# DIMNode062013.net
KiCad netlist of a schematic drawn in Altium Designer
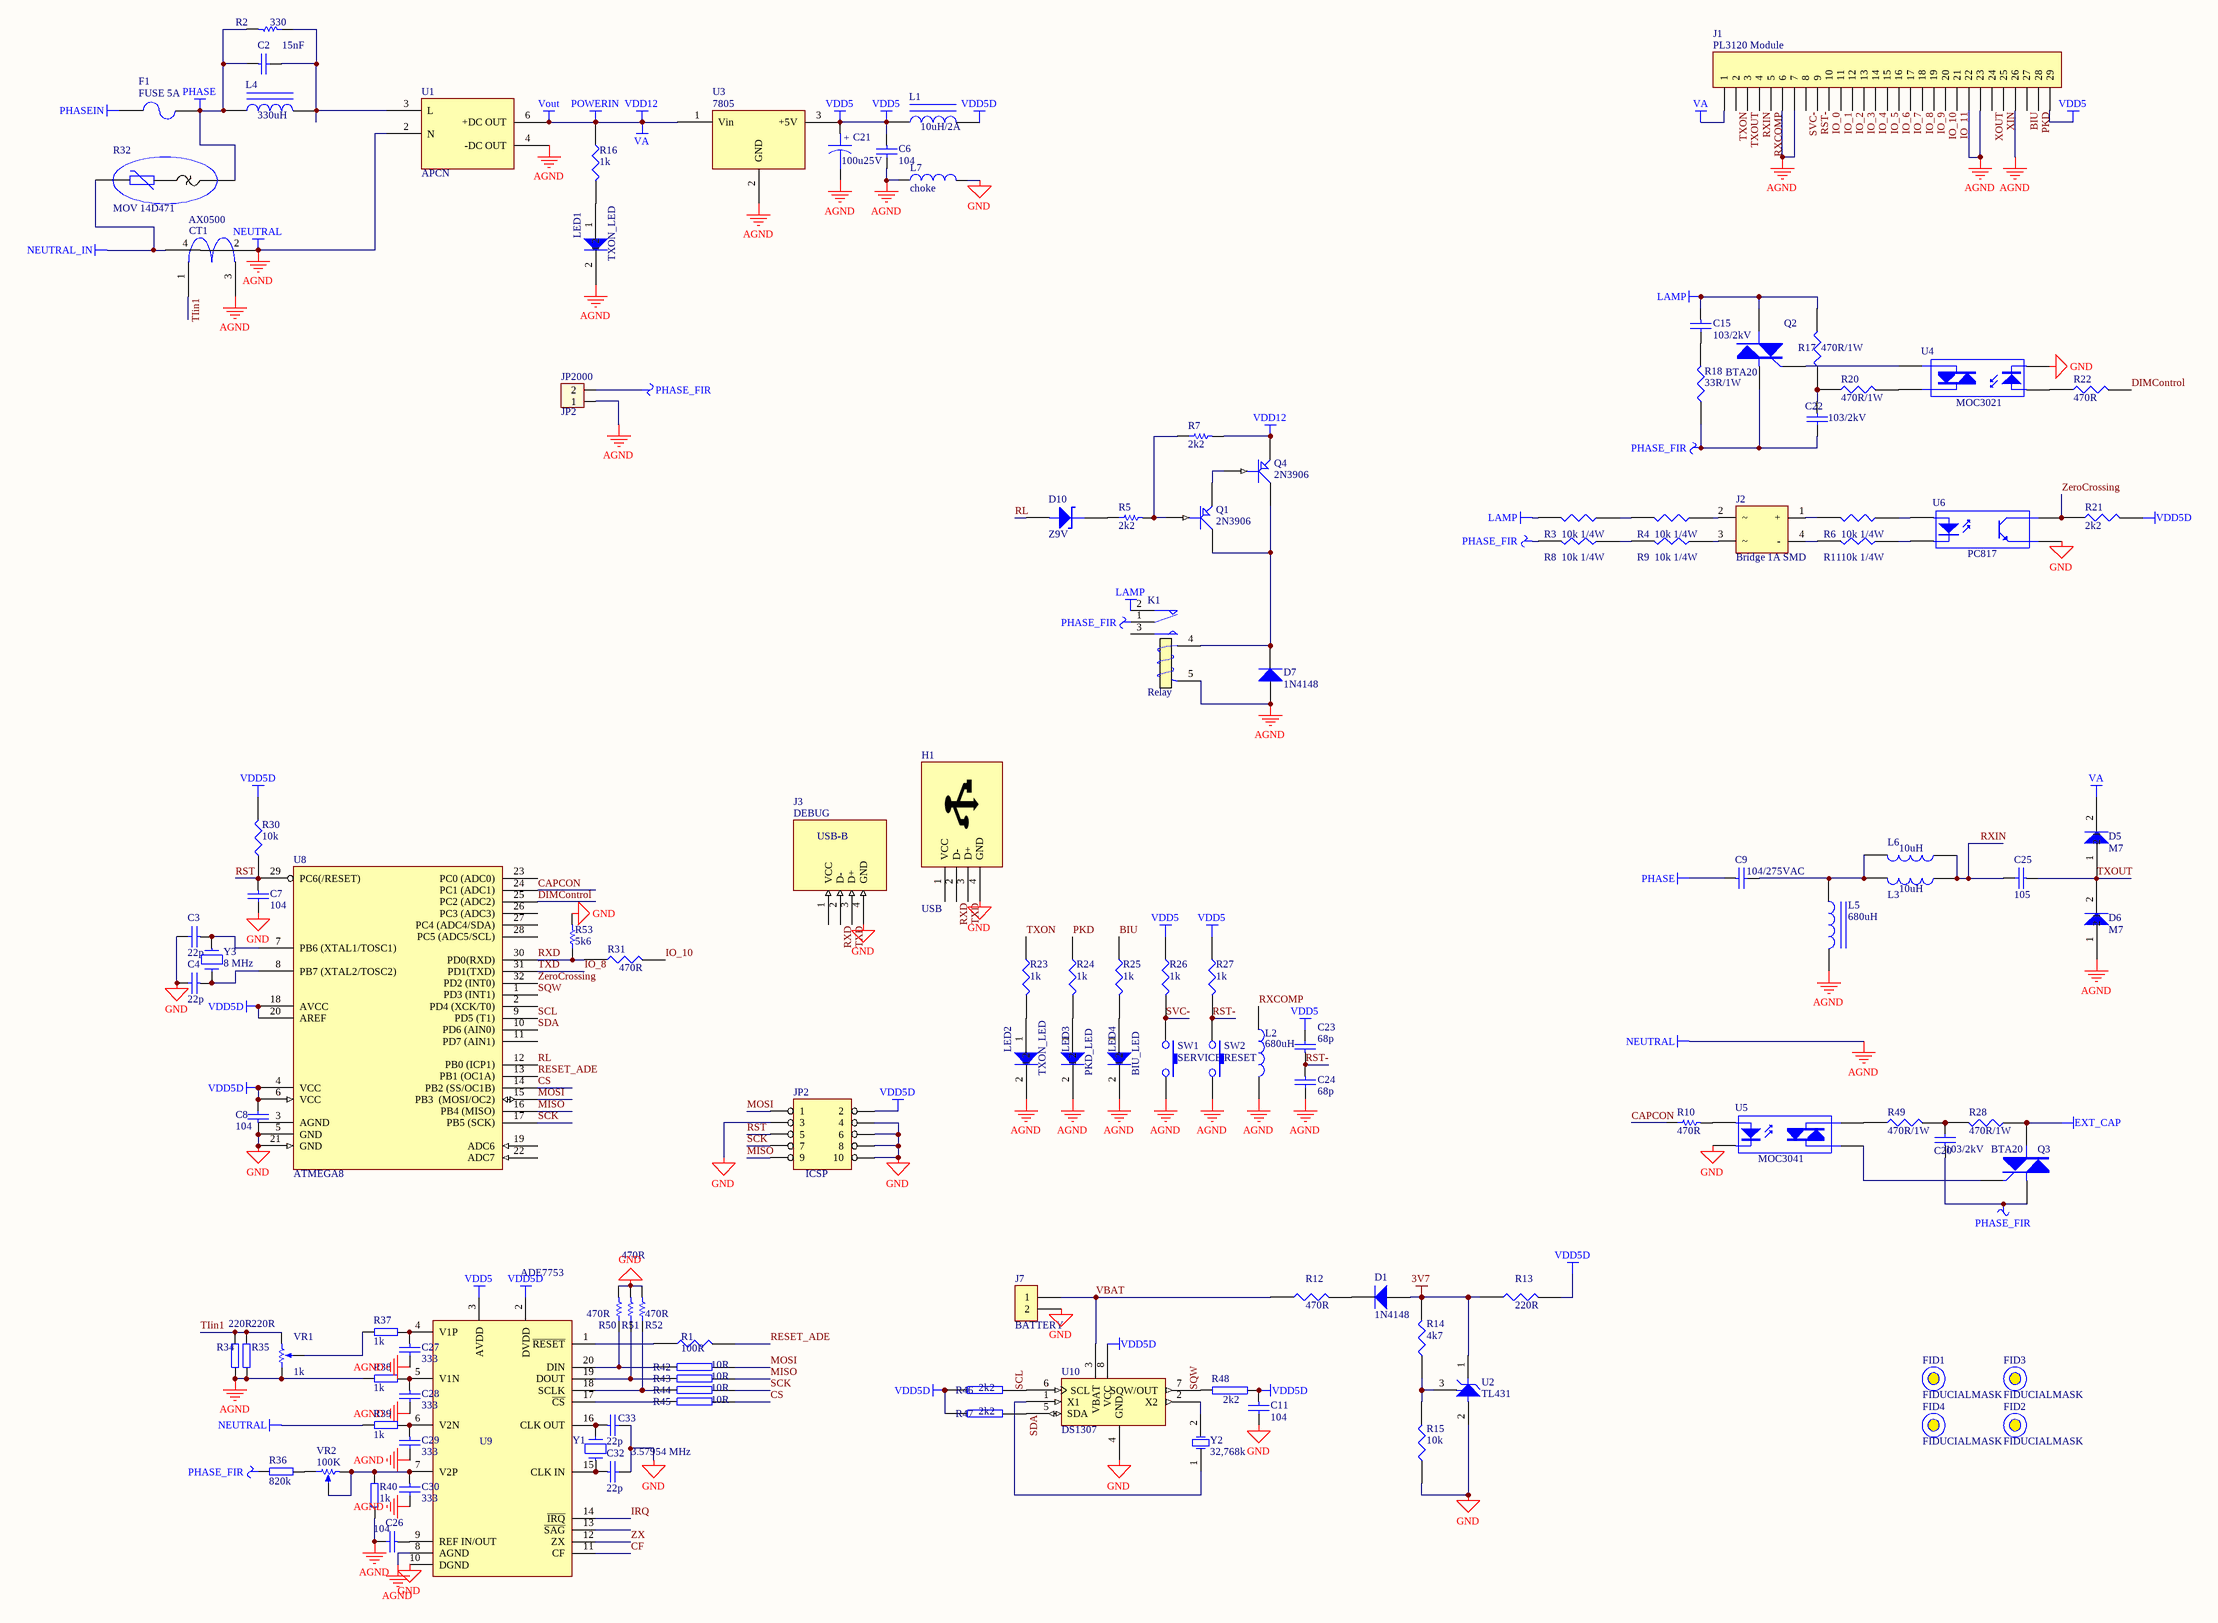
[diagram p0: DIMNode062013.SchDoc]

(export (version "E")
  (design (tool "Eeschema 10.0.6"))
  (components
    (comp (ref "C2")
      (value "15nF")
      (footprint "CAPNTO5.08-7.37x3.94")
      (description "Capacitor")
      (libsource (lib "*") (part "CAP"))
    )
    (comp (ref "C3") (value "22p") (footprint "2012[0805]") (libsource (lib "") (part "CAP_1")))
    (comp (ref "C4") (value "22p") (footprint "2012[0805]") (libsource (lib "") (part "CAP_1")))
    (comp (ref "C6")
      (value "104")
      (footprint "2012[0805]")
      (description "Capacitor")
      (libsource (lib "*") (part "CAP"))
    )
    (comp (ref "C7")
      (value "104")
      (footprint "2012[0805]")
      (description "Capacitor")
      (libsource (lib "*") (part "CAP"))
    )
    (comp (ref "C8")
      (value "104")
      (footprint "2012[0805]")
      (description "Capacitor")
      (libsource (lib "*") (part "CAP"))
    )
    (comp (ref "C9")
      (value "104/275VAC")
      (footprint "100n400v")
      (description "Capacitor")
      (libsource (lib "*") (part "CAP"))
    )
    (comp (ref "C11")
      (value "104")
      (footprint "2012[0805]")
      (description "Capacitor")
      (libsource (lib "*") (part "CAP"))
    )
    (comp (ref "C15")
      (value "103/2kV")
      (footprint "104TO")
      (description "Capacitor")
      (libsource (lib "*") (part "CAP"))
    )
    (comp (ref "C20")
      (value "103/2kV")
      (footprint "104TO")
      (description "Capacitor")
      (libsource (lib "*") (part "CAP"))
    )
    (comp (ref "C21")
      (value "100u25V")
      (footprint "TC7360-2924")
      (description "Capacitor")
      (libsource (lib "*") (part "CAPACITOR POL"))
    )
    (comp (ref "C22")
      (value "103/2kV")
      (footprint "104TO")
      (description "Capacitor")
      (libsource (lib "*") (part "CAP"))
    )
    (comp (ref "C23")
      (value "68p")
      (footprint "2012[0805]")
      (description "Capacitor")
      (libsource (lib "*") (part "CAP"))
    )
    (comp (ref "C24")
      (value "68p")
      (footprint "2012[0805]")
      (description "Capacitor")
      (libsource (lib "*") (part "CAP"))
    )
    (comp (ref "C25")
      (value "105")
      (footprint "CSIP3")
      (description "Capacitor")
      (libsource (lib "*") (part "CAP"))
    )
    (comp (ref "C26") (value "104") (footprint "2012[0805]") (libsource (lib "") (part "CAP_1")))
    (comp (ref "C27") (value "333") (footprint "2012[0805]") (libsource (lib "") (part "CAP_1")))
    (comp (ref "C28") (value "333") (footprint "2012[0805]") (libsource (lib "") (part "CAP_1")))
    (comp (ref "C29") (value "333") (footprint "2012[0805]") (libsource (lib "") (part "CAP_1")))
    (comp (ref "C30") (value "333") (footprint "2012[0805]") (libsource (lib "") (part "CAP_1")))
    (comp (ref "C32") (value "22p") (footprint "2012[0805]") (libsource (lib "") (part "CAP_1")))
    (comp (ref "C33") (value "22p") (footprint "2012[0805]") (libsource (lib "") (part "CAP_1")))
    (comp (ref "CT1") (value "AX0500") (footprint "CT-NHO") (libsource (lib "Schlib1") (part "AX-0500")))
    (comp (ref "D1")
      (value "1N4148")
      (footprint "SOD-80/MLL34")
      (description "1 Amp General Purpose Rectifier")
      (fields (field (name "PUBLISHER") "Altium Limited"))
      (libsource (lib "*") (part "Diode 1N4007"))
    )
    (comp (ref "D5") (value "M7") (footprint "MELF-D5022-2009") (libsource (lib "*") (part "DIODE")))
    (comp (ref "D6") (value "M7") (footprint "MELF-D5022-2009") (libsource (lib "*") (part "DIODE")))
    (comp (ref "D7")
      (value "1N4148")
      (footprint "SOD-80/MLL34")
      (description "1 Amp General Purpose Rectifier")
      (fields (field (name "PUBLISHER") "Altium Limited"))
      (libsource (lib "*") (part "Diode 1N4007"))
    )
    (comp (ref "D10")
      (value "Z9V")
      (footprint "SOD-80/MLL34")
      (description "Zener Diode")
      (libsource (lib "*") (part "ZENER2"))
    )
    (comp (ref "F1")
      (value "FUSE 5A")
      (footprint "FUSE2")
      (description "Fuse")
      (libsource (lib "*") (part "FUSE2"))
    )
    (comp (ref "FID1")
      (value "FIDUCIALMASK")
      (footprint "FIDUCIALMASK")
      (libsource (lib "*") (part "FIDUCIALMASK"))
    )
    (comp (ref "FID2")
      (value "FIDUCIALMASK")
      (footprint "FIDUCIALMASK")
      (libsource (lib "*") (part "FIDUCIALMASK"))
    )
    (comp (ref "FID3")
      (value "FIDUCIALMASK")
      (footprint "FIDUCIALMASK")
      (libsource (lib "*") (part "FIDUCIALMASK"))
    )
    (comp (ref "FID4")
      (value "FIDUCIALMASK")
      (footprint "FIDUCIALMASK")
      (libsource (lib "*") (part "FIDUCIALMASK"))
    )
    (comp (ref "H1") (value "USB") (footprint "USB-B-STRANGE") (libsource (lib "Schematic") (part "USB")))
    (comp (ref "J1")
      (value "PL3120 Module")
      (footprint "ECHELONMODULE")
      (description "Connector")
      (libsource (lib "*") (part "CON29"))
    )
    (comp (ref "J2")
      (value "Bridge 1A SMD")
      (footprint "CAUSMD")
      (description "Diode Bridge")
      (libsource (lib "Schematic") (part "Diode Bridge Flate"))
    )
    (comp (ref "J3") (value "DEBUG") (footprint "SJ-3515") (libsource (lib "*") (part "USB_B")))
    (comp (ref "J7")
      (value "BATTERY")
      (footprint "pincucao")
      (description "Connector")
      (libsource (lib "*") (part "CON2"))
    )
    (comp (ref "JP2") (value "ICSP") (footprint "IDC10") (libsource (lib "*") (part "HEADER 5X2")))
    (comp (ref "JP2000")
      (value "JP2")
      (footprint "HED2")
      (description "Connector 2")
      (libsource (lib "syhaunguyen") (part "Con2"))
    )
    (comp (ref "K1")
      (value "Relay")
      (footprint "Relayvuong")
      (description "SPDT Relay")
      (fields (field (name "PUBLISHER") "Altium Limited"))
      (libsource (lib "*") (part "Relay"))
    )
    (comp (ref "L1") (value "10uH/2A") (libsource (lib "*") (part "INDUCTOR IRON")))
    (comp (ref "L2") (value "680uH") (footprint "AXIAL0.4") (libsource (lib "*") (part "INDUCTOR")))
    (comp (ref "L3") (value "10uH") (footprint "AXIAL0.4") (libsource (lib "*") (part "INDUCTOR")))
    (comp (ref "L4") (value "330uH") (footprint "CAMTRONDUNG") (libsource (lib "*") (part "INDUCTOR IRON")))
    (comp (ref "L5") (value "680uH") (footprint "axial0.4") (libsource (lib "*") (part "INDUCTOR IRON")))
    (comp (ref "L6") (value "10uH") (footprint "AXIAL0.4") (libsource (lib "*") (part "INDUCTOR")))
    (comp (ref "L7")
      (value "choke")
      (footprint "axial0.3")
      (fields (field (name "PUBLISHER") "Altium Limited"))
      (libsource (lib "Miscellaneous Devices") (part "Inductor"))
    )
    (comp (ref "LED1") (value "TXON_LED") (footprint "LED0805") (libsource (lib "*") (part "DIODE")))
    (comp (ref "LED2") (value "TXON_LED") (footprint "LED0805") (libsource (lib "*") (part "DIODE")))
    (comp (ref "LED3") (value "PKD_LED") (footprint "LED0805") (libsource (lib "*") (part "DIODE")))
    (comp (ref "LED4") (value "BIU_LED") (footprint "LED0805") (libsource (lib "*") (part "DIODE")))
    (comp (ref "Q1")
      (value "2N3906")
      (footprint "SOT-23")
      (description "PNP Transistor")
      (libsource (lib "*") (part "PNP1"))
    )
    (comp (ref "Q2") (value "BTA20") (footprint "TO254") (libsource (lib "*") (part "TRIAC")))
    (comp (ref "Q3") (value "BTA20") (footprint "TO254") (libsource (lib "*") (part "TRIAC")))
    (comp (ref "Q4")
      (value "2N3906")
      (footprint "SOT-23")
      (description "PNP Transistor")
      (libsource (lib "*") (part "PNP1"))
    )
    (comp (ref "R1") (value "100R") (footprint "2012[0805]") (libsource (lib "*") (part "RES1")))
    (comp (ref "R2")
      (value "330")
      (footprint "3216[1206]")
      (description "Semiconductor Resistor")
      (fields (field (name "PUBLISHER") "Altium Limited"))
      (libsource (lib "*") (part "Res Semi"))
    )
    (comp (ref "R3") (value "10k 1/4W") (footprint "3216[1206]") (libsource (lib "*") (part "RES1")))
    (comp (ref "R4") (value "10k 1/4W") (footprint "3216[1206]") (libsource (lib "*") (part "RES1")))
    (comp (ref "R5")
      (value "2k2")
      (footprint "2012[0805]")
      (description "Semiconductor Resistor")
      (fields (field (name "PUBLISHER") "Altium Limited"))
      (libsource (lib "*") (part "Res Semi"))
    )
    (comp (ref "R6") (value "10k 1/4W") (footprint "3216[1206]") (libsource (lib "*") (part "RES1")))
    (comp (ref "R7")
      (value "2k2")
      (footprint "2012[0805]")
      (description "Semiconductor Resistor")
      (fields (field (name "PUBLISHER") "Altium Limited"))
      (libsource (lib "*") (part "Res Semi"))
    )
    (comp (ref "R8") (value "10k 1/4W") (footprint "3216[1206]") (libsource (lib "*") (part "RES1")))
    (comp (ref "R9") (value "10k 1/4W") (footprint "3216[1206]") (libsource (lib "*") (part "RES1")))
    (comp (ref "R10")
      (value "470R")
      (footprint "2012[0805]")
      (description "Semiconductor Resistor")
      (fields (field (name "PUBLISHER") "Altium Limited"))
      (libsource (lib "*") (part "Res Semi"))
    )
    (comp (ref "R11") (value "10k 1/4W") (footprint "3216[1206]") (libsource (lib "*") (part "RES1")))
    (comp (ref "R12") (value "470R") (footprint "2012[0805]") (libsource (lib "*") (part "RES1")))
    (comp (ref "R13") (value "220R") (footprint "2012[0805]") (libsource (lib "*") (part "RES1")))
    (comp (ref "R14") (value "4k7") (footprint "2012[0805]") (libsource (lib "*") (part "RES1")))
    (comp (ref "R15") (value "10k") (footprint "2012[0805]") (libsource (lib "*") (part "RES1")))
    (comp (ref "R16") (value "1k") (footprint "2012[0805]") (libsource (lib "*") (part "RES1")))
    (comp (ref "R17") (value "470R/1W") (footprint "AXIAL0.5") (libsource (lib "*") (part "RES1")))
    (comp (ref "R18") (value "33R/1W") (footprint "R1W_dung") (libsource (lib "*") (part "RES1")))
    (comp (ref "R20") (value "470R/1W") (footprint "R1W_DUNG") (libsource (lib "*") (part "RES1")))
    (comp (ref "R21") (value "2k2") (footprint "2012[0805]") (libsource (lib "*") (part "RES1")))
    (comp (ref "R22") (value "470R") (footprint "2012[0805]") (libsource (lib "*") (part "RES1")))
    (comp (ref "R23") (value "1k") (footprint "2012[0805]") (libsource (lib "*") (part "RES1")))
    (comp (ref "R24") (value "1k") (footprint "2012[0805]") (libsource (lib "*") (part "RES1")))
    (comp (ref "R25") (value "1k") (footprint "2012[0805]") (libsource (lib "*") (part "RES1")))
    (comp (ref "R26") (value "1k") (footprint "2012[0805]") (libsource (lib "*") (part "RES1")))
    (comp (ref "R27") (value "1k") (footprint "2012[0805]") (libsource (lib "*") (part "RES1")))
    (comp (ref "R28") (value "470R/1W") (footprint "R1W_dung") (libsource (lib "*") (part "RES1")))
    (comp (ref "R30") (value "10k") (footprint "2012[0805]") (libsource (lib "*") (part "RES1")))
    (comp (ref "R31") (value "470R") (footprint "2012[0805]") (libsource (lib "*") (part "RES1")))
    (comp (ref "R32") (value "MOV 14D471") (footprint "MOV471") (libsource (lib "*") (part "MOV")))
    (comp (ref "R34") (value "220R") (footprint "2012[0805]") (libsource (lib "*") (part "RES2")))
    (comp (ref "R35") (value "220R") (footprint "2012[0805]") (libsource (lib "*") (part "RES2")))
    (comp (ref "R36") (value "820k") (footprint "1206") (libsource (lib "*") (part "RES2")))
    (comp (ref "R37") (value "1k") (footprint "2012[0805]") (libsource (lib "*") (part "RES2")))
    (comp (ref "R38") (value "1k") (footprint "2012[0805]") (libsource (lib "*") (part "RES2")))
    (comp (ref "R39") (value "1k") (footprint "2012[0805]") (libsource (lib "*") (part "RES2")))
    (comp (ref "R40") (value "1k") (footprint "2012[0805]") (libsource (lib "*") (part "RES2")))
    (comp (ref "R42") (value "10R") (footprint "2012[0805]") (libsource (lib "") (part "RES2_1")))
    (comp (ref "R43") (value "10R") (footprint "2012[0805]") (libsource (lib "") (part "RES2_1")))
    (comp (ref "R44") (value "10R") (footprint "2012[0805]") (libsource (lib "") (part "RES2_1")))
    (comp (ref "R45") (value "10R") (footprint "2012[0805]") (libsource (lib "") (part "RES2_1")))
    (comp (ref "R46") (value "2k2") (footprint "2012[0805]") (libsource (lib "") (part "RES2_1")))
    (comp (ref "R47") (value "2k2") (footprint "2012[0805]") (libsource (lib "") (part "RES2_1")))
    (comp (ref "R48") (value "2k2") (footprint "2012[0805]") (libsource (lib "") (part "RES2_2")))
    (comp (ref "R49") (value "470R/1W") (footprint "R1W_DUNG") (libsource (lib "*") (part "RES1")))
    (comp (ref "R50")
      (value "470R")
      (footprint "2012[0805]")
      (description "Semiconductor Resistor")
      (fields (field (name "PUBLISHER") "*"))
      (libsource (lib "*") (part "Res Semi"))
    )
    (comp (ref "R51")
      (value "470R")
      (footprint "2012[0805]")
      (description "Semiconductor Resistor")
      (fields (field (name "PUBLISHER") "*"))
      (libsource (lib "*") (part "Res Semi"))
    )
    (comp (ref "R52")
      (value "470R")
      (footprint "2012[0805]")
      (description "Semiconductor Resistor")
      (fields (field (name "PUBLISHER") "*"))
      (libsource (lib "*") (part "Res Semi"))
    )
    (comp (ref "R53")
      (value "5k6")
      (footprint "2012[0805]")
      (description "Semiconductor Resistor")
      (fields (field (name "PUBLISHER") "*"))
      (libsource (lib "*") (part "Res Semi"))
    )
    (comp (ref "SW1") (value "SERVICE") (footprint "CTCHIPNGANG") (libsource (lib "*") (part "SW-PB")))
    (comp (ref "SW2") (value "RESET") (footprint "CTCHIPNGANG") (libsource (lib "*") (part "SW-PB")))
    (comp (ref "U1") (value "APCN") (footprint "APCN") (libsource (lib "Node v2013") (part "Component_1")))
    (comp (ref "U2")
      (value "TL431")
      (footprint "TL431")
      (description "Adjustable Precision Shunt Regulator")
      (libsource (lib "*") (part "TL431"))
    )
    (comp (ref "U3") (value "7805") (footprint "J7805") (libsource (lib "*") (part "MC7805T")))
    (comp (ref "U4") (value "MOC3021") (footprint "DIP6") (libsource (lib "*") (part "OPTOTRIAC")))
    (comp (ref "U5") (value "MOC3041") (footprint "DIP6") (libsource (lib "*") (part "OPTOTRIAC")))
    (comp (ref "U6")
      (value "PC817")
      (footprint "TLP521")
      (description "Optoisolator")
      (libsource (lib "*") (part "OPTOISO1"))
    )
    (comp (ref "U8")
      (value "ATMEGA8")
      (footprint "ATMEGA8")
      (description "TQFP package")
      (libsource (lib "*") (part "ATMEGA8-A"))
    )
    (comp (ref "U9") (value "ADE7753") (footprint "ADE775X") (libsource (lib "*") (part "ADE775X")))
    (comp (ref "U10")
      (value "DS1307")
      (footprint "SO-8")
      (description "64x8 SERIAL REAL TIME CLOCK")
      (libsource (lib "*") (part "DS1307(8)"))
    )
    (comp (ref "VR1")
      (value "1k")
      (footprint "BTXANH")
      (description "Potentiometer")
      (fields (field (name "PUBLISHER") "*"))
      (libsource (lib "*") (part "RPot"))
    )
    (comp (ref "VR2")
      (value "100K")
      (footprint "BTXANH")
      (description "Potentiometer")
      (fields (field (name "PUBLISHER") "*"))
      (libsource (lib "*") (part "RPot"))
    )
    (comp (ref "Y1")
      (value "3.57954 MHz")
      (footprint "XTAL")
      (description "Crystal")
      (libsource (lib "*") (part "CRYSTAL"))
    )
    (comp (ref "Y2")
      (value "32,768k")
      (footprint "R38")
      (description "Crystal Oscillator")
      (fields (field (name "PUBLISHER") "Altium Limited"))
      (libsource (lib "Miscellaneous Devices") (part "XTAL"))
    )
    (comp (ref "Y3")
      (value "8 MHz")
      (footprint "XTAL")
      (description "Crystal")
      (libsource (lib "*") (part "CRYSTAL"))
    )
  )
  (nets
    (net (code "1") (name "/BIU") (class "Default")
      (node (ref "J1") (pin "27") (pinfunction "27_27") (pintype "passive"))
      (node (ref "R25") (pin "1") (pinfunction "1_1") (pintype "passive"))
    )
    (net (code "2") (name "/CAPCON") (class "Default")
      (node (ref "R10") (pin "1") (pinfunction "1_1") (pintype "passive"))
      (node (ref "U8") (pin "24") (pinfunction "PC1_(ADC1)_24") (pintype "passive"))
    )
    (net (code "3") (name "/CF") (class "Default")
      (node (ref "U9") (pin "11") (pinfunction "CF_11") (pintype "passive"))
    )
    (net (code "4") (name "/CS") (class "Default")
      (node (ref "R45") (pin "1") (pinfunction "1_1") (pintype "passive"))
      (node (ref "U8") (pin "14") (pinfunction "PB2_(SS/OC1B)_14") (pintype "passive"))
    )
    (net (code "5") (name "/DIMControl") (class "Default")
      (node (ref "R22") (pin "2") (pinfunction "2_2") (pintype "passive"))
      (node (ref "U8") (pin "25") (pinfunction "PC2_(ADC2)_25") (pintype "passive"))
    )
    (net (code "6") (name "/IO_0") (class "Default")
      (node (ref "J1") (pin "10") (pinfunction "10_10") (pintype "passive"))
    )
    (net (code "7") (name "/IO_1") (class "Default")
      (node (ref "J1") (pin "11") (pinfunction "11_11") (pintype "passive"))
    )
    (net (code "8") (name "/IO_2") (class "Default")
      (node (ref "J1") (pin "12") (pinfunction "12_12") (pintype "passive"))
    )
    (net (code "9") (name "/IO_3") (class "Default")
      (node (ref "J1") (pin "13") (pinfunction "13_13") (pintype "passive"))
    )
    (net (code "10") (name "/IO_4") (class "Default")
      (node (ref "J1") (pin "14") (pinfunction "14_14") (pintype "passive"))
    )
    (net (code "11") (name "/IO_5") (class "Default")
      (node (ref "J1") (pin "15") (pinfunction "15_15") (pintype "passive"))
    )
    (net (code "12") (name "/IO_6") (class "Default")
      (node (ref "J1") (pin "16") (pinfunction "16_16") (pintype "passive"))
    )
    (net (code "13") (name "/IO_7") (class "Default")
      (node (ref "J1") (pin "17") (pinfunction "17_17") (pintype "passive"))
    )
    (net (code "14") (name "/IO_8") (class "Default")
      (node (ref "H1") (pin "3") (pinfunction "D+_3") (pintype "passive"))
      (node (ref "J1") (pin "18") (pinfunction "18_18") (pintype "passive"))
      (node (ref "J3") (pin "3") (pinfunction "D+_3") (pintype "input"))
      (node (ref "U8") (pin "31") (pinfunction "PD1(TXD)_31") (pintype "passive"))
    )
    (net (code "15") (name "/IO_9") (class "Default")
      (node (ref "J1") (pin "19") (pinfunction "19_19") (pintype "passive"))
    )
    (net (code "16") (name "/IO_10") (class "Default")
      (node (ref "J1") (pin "20") (pinfunction "20_20") (pintype "passive"))
      (node (ref "R31") (pin "2") (pinfunction "2_2") (pintype "passive"))
    )
    (net (code "17") (name "/IO_11") (class "Default")
      (node (ref "J1") (pin "21") (pinfunction "21_21") (pintype "passive"))
    )
    (net (code "18") (name "/IRQ") (class "Default")
      (node (ref "U9") (pin "14") (pinfunction "~{IRQ}_14") (pintype "passive"))
    )
    (net (code "19") (name "/MISO") (class "Default")
      (node (ref "JP2") (pin "9") (pinfunction "9_9") (pintype "passive"))
      (node (ref "R43") (pin "1") (pinfunction "1_1") (pintype "passive"))
      (node (ref "U8") (pin "16") (pinfunction "PB4_(MISO)_16") (pintype "passive"))
    )
    (net (code "20") (name "/MOSI") (class "Default")
      (node (ref "JP2") (pin "1") (pinfunction "1_1") (pintype "passive"))
      (node (ref "R42") (pin "1") (pinfunction "1_1") (pintype "passive"))
      (node (ref "U8") (pin "15") (pinfunction "PB3__(MOSI/OC2)_15") (pintype "bidirectional"))
    )
    (net (code "21") (name "/PKD") (class "Default")
      (node (ref "J1") (pin "28") (pinfunction "28_28") (pintype "passive"))
      (node (ref "R24") (pin "1") (pinfunction "1_1") (pintype "passive"))
    )
    (net (code "22") (name "/RESET_ADE") (class "Default")
      (node (ref "R1") (pin "2") (pinfunction "2_2") (pintype "passive"))
      (node (ref "U8") (pin "13") (pinfunction "PB1_(OC1A)_13") (pintype "passive"))
    )
    (net (code "23") (name "/RL") (class "Default")
      (node (ref "D10") (pin "1") (pinfunction "A_1") (pintype "passive"))
      (node (ref "U8") (pin "12") (pinfunction "PB0_(ICP1)_12") (pintype "passive"))
    )
    (net (code "24") (name "/RST") (class "Default")
      (node (ref "C7") (pin "1") (pinfunction "1_1") (pintype "passive"))
      (node (ref "JP2") (pin "5") (pinfunction "5_5") (pintype "passive"))
      (node (ref "R30") (pin "1") (pinfunction "1_1") (pintype "passive"))
      (node (ref "U8") (pin "29") (pinfunction "PC6(/RESET)_29") (pintype "passive"))
    )
    (net (code "25") (name "/RST-") (class "Default")
      (node (ref "C23") (pin "1") (pinfunction "1_1") (pintype "passive"))
      (node (ref "C24") (pin "1") (pinfunction "1_1") (pintype "passive"))
      (node (ref "J1") (pin "9") (pinfunction "9_9") (pintype "passive"))
      (node (ref "R27") (pin "2") (pinfunction "2_2") (pintype "passive"))
      (node (ref "SW2") (pin "1") (pinfunction "1_1") (pintype "passive"))
    )
    (net (code "26") (name "/RXCOMP") (class "Default")
      (node (ref "J1") (pin "5") (pinfunction "5_5") (pintype "passive"))
      (node (ref "L2") (pin "1") (pinfunction "1_1") (pintype "passive"))
    )
    (net (code "27") (name "/RXD") (class "Default")
      (node (ref "H1") (pin "2") (pinfunction "D-_2") (pintype "passive"))
      (node (ref "J3") (pin "2") (pinfunction "D-_2") (pintype "input"))
      (node (ref "R31") (pin "1") (pinfunction "1_1") (pintype "passive"))
      (node (ref "R53") (pin "1") (pinfunction "1_1") (pintype "passive"))
      (node (ref "U8") (pin "30") (pinfunction "PD0(RXD)_30") (pintype "passive"))
    )
    (net (code "28") (name "/RXIN") (class "Default")
      (node (ref "C25") (pin "2") (pinfunction "2_2") (pintype "passive"))
      (node (ref "J1") (pin "4") (pinfunction "4_4") (pintype "passive"))
      (node (ref "L3") (pin "1") (pinfunction "1_1") (pintype "passive"))
      (node (ref "L6") (pin "1") (pinfunction "1_1") (pintype "passive"))
    )
    (net (code "29") (name "/SCK") (class "Default")
      (node (ref "JP2") (pin "7") (pinfunction "7_7") (pintype "passive"))
      (node (ref "R44") (pin "1") (pinfunction "1_1") (pintype "passive"))
      (node (ref "U8") (pin "17") (pinfunction "PB5_(SCK)_17") (pintype "passive"))
    )
    (net (code "30") (name "/SCL") (class "Default")
      (node (ref "R46") (pin "1") (pinfunction "1_1") (pintype "passive"))
      (node (ref "U10") (pin "6") (pinfunction "SCL_6") (pintype "input"))
      (node (ref "U8") (pin "9") (pinfunction "PD5_(T1)_9") (pintype "passive"))
    )
    (net (code "31") (name "/SDA") (class "Default")
      (node (ref "R47") (pin "1") (pinfunction "1_1") (pintype "passive"))
      (node (ref "U10") (pin "5") (pinfunction "SDA_5") (pintype "bidirectional"))
      (node (ref "U8") (pin "10") (pinfunction "PD6_(AIN0)_10") (pintype "passive"))
    )
    (net (code "32") (name "/SQW") (class "Default")
      (node (ref "R48") (pin "1") (pinfunction "1_1") (pintype "passive"))
      (node (ref "U10") (pin "7") (pinfunction "SQW/OUT_7") (pintype "output"))
      (node (ref "U8") (pin "1") (pinfunction "PD3_(INT1)_1") (pintype "passive"))
    )
    (net (code "33") (name "/SVC-") (class "Default")
      (node (ref "J1") (pin "8") (pinfunction "8_8") (pintype "passive"))
      (node (ref "R26") (pin "2") (pinfunction "2_2") (pintype "passive"))
      (node (ref "SW1") (pin "1") (pinfunction "1_1") (pintype "passive"))
    )
    (net (code "34") (name "/TIin1") (class "Default")
      (node (ref "CT1") (pin "1") (pinfunction "OUT1_1") (pintype "passive"))
      (node (ref "R34") (pin "2") (pinfunction "2_2") (pintype "passive"))
      (node (ref "R35") (pin "2") (pinfunction "2_2") (pintype "passive"))
      (node (ref "VR1") (pin "3") (pinfunction "BOT_3") (pintype "passive"))
    )
    (net (code "35") (name "/TXON") (class "Default")
      (node (ref "J1") (pin "2") (pinfunction "2_2") (pintype "passive"))
      (node (ref "R23") (pin "1") (pinfunction "1_1") (pintype "passive"))
    )
    (net (code "36") (name "/TXOUT") (class "Default")
      (node (ref "C25") (pin "1") (pinfunction "1_1") (pintype "passive"))
      (node (ref "D5") (pin "1") (pinfunction "1_1") (pintype "passive"))
      (node (ref "D6") (pin "2") (pinfunction "2_2") (pintype "passive"))
      (node (ref "J1") (pin "3") (pinfunction "3_3") (pintype "passive"))
    )
    (net (code "37") (name "/VBAT") (class "Default")
      (node (ref "J7") (pin "1") (pinfunction "1_1") (pintype "passive"))
      (node (ref "R12") (pin "1") (pinfunction "1_1") (pintype "passive"))
      (node (ref "U10") (pin "3") (pinfunction "VBAT_3") (pintype "power_in"))
    )
    (net (code "38") (name "/XIN") (class "Default")
      (node (ref "J1") (pin "25") (pinfunction "25_25") (pintype "passive"))
    )
    (net (code "39") (name "/XOUT") (class "Default")
      (node (ref "J1") (pin "24") (pinfunction "24_24") (pintype "passive"))
    )
    (net (code "40") (name "/ZX") (class "Default")
      (node (ref "U9") (pin "12") (pinfunction "ZX_12") (pintype "passive"))
    )
    (net (code "41") (name "/ZeroCrossing") (class "Default")
      (node (ref "R21") (pin "1") (pinfunction "1_1") (pintype "passive"))
      (node (ref "U6") (pin "3") (pinfunction "C_3") (pintype "passive"))
      (node (ref "U8") (pin "32") (pinfunction "PD2_(INT0)_32") (pintype "passive"))
    )
    (net (code "42") (name "3V7") (class "Default")
      (node (ref "D1") (pin "1") (pinfunction "A_1") (pintype "passive"))
      (node (ref "R13") (pin "1") (pinfunction "1_1") (pintype "passive"))
      (node (ref "R14") (pin "2") (pinfunction "2_2") (pintype "passive"))
      (node (ref "U2") (pin "1") (pinfunction "K_1") (pintype "passive"))
    )
    (net (code "43") (name "AGND") (class "Default")
      (node (ref "C21") (pin "2") (pinfunction "2_2") (pintype "passive"))
      (node (ref "C24") (pin "2") (pinfunction "2_2") (pintype "passive"))
      (node (ref "C26") (pin "2") (pinfunction "2_2") (pintype "passive"))
      (node (ref "C27") (pin "2") (pinfunction "2_2") (pintype "passive"))
      (node (ref "C28") (pin "2") (pinfunction "2_2") (pintype "passive"))
      (node (ref "C29") (pin "2") (pinfunction "2_2") (pintype "passive"))
      (node (ref "C30") (pin "2") (pinfunction "2_2") (pintype "passive"))
      (node (ref "C6") (pin "2") (pinfunction "2_2") (pintype "passive"))
      (node (ref "CT1") (pin "2") (pinfunction "ACin_2") (pintype "passive"))
      (node (ref "CT1") (pin "3") (pinfunction "OUT2_3") (pintype "passive"))
      (node (ref "D6") (pin "1") (pinfunction "1_1") (pintype "passive"))
      (node (ref "D7") (pin "1") (pinfunction "A_1") (pintype "passive"))
      (node (ref "J1") (pin "22") (pinfunction "22_22") (pintype "passive"))
      (node (ref "J1") (pin "23") (pinfunction "23_23") (pintype "passive"))
      (node (ref "J1") (pin "26") (pinfunction "26_26") (pintype "passive"))
      (node (ref "J1") (pin "6") (pinfunction "6_6") (pintype "passive"))
      (node (ref "J1") (pin "7") (pinfunction "7_7") (pintype "passive"))
      (node (ref "JP2000") (pin "1") (pinfunction "1_1") (pintype "passive"))
      (node (ref "K1") (pin "5") (pinfunction "T2_5") (pintype "passive"))
      (node (ref "L2") (pin "2") (pinfunction "2_2") (pintype "passive"))
      (node (ref "L5") (pin "2") (pinfunction "2_2") (pintype "passive"))
      (node (ref "L7") (pin "1") (pinfunction "1_1") (pintype "passive"))
      (node (ref "LED1") (pin "2") (pinfunction "2_2") (pintype "passive"))
      (node (ref "LED2") (pin "2") (pinfunction "2_2") (pintype "passive"))
      (node (ref "LED3") (pin "2") (pinfunction "2_2") (pintype "passive"))
      (node (ref "LED4") (pin "2") (pinfunction "2_2") (pintype "passive"))
      (node (ref "R34") (pin "1") (pinfunction "1_1") (pintype "passive"))
      (node (ref "R35") (pin "1") (pinfunction "1_1") (pintype "passive"))
      (node (ref "R38") (pin "2") (pinfunction "2_2") (pintype "passive"))
      (node (ref "R39") (pin "2") (pinfunction "2_2") (pintype "passive"))
      (node (ref "R40") (pin "1") (pinfunction "1_1") (pintype "passive"))
      (node (ref "SW1") (pin "2") (pinfunction "2_2") (pintype "passive"))
      (node (ref "SW2") (pin "2") (pinfunction "2_2") (pintype "passive"))
      (node (ref "U1") (pin "2") (pinfunction "N_2") (pintype "passive"))
      (node (ref "U1") (pin "4") (pinfunction "-DC_OUT_4") (pintype "passive"))
      (node (ref "U3") (pin "2") (pinfunction "GND_2") (pintype "passive"))
      (node (ref "U9") (pin "8") (pinfunction "AGND_8") (pintype "passive"))
      (node (ref "VR1") (pin "1") (pinfunction "TOP_1") (pintype "passive"))
    )
    (net (code "44") (name "EXT_CAP") (class "Default")
      (node (ref "Q3") (pin "2") (pinfunction "T_2") (pintype "passive"))
      (node (ref "R28") (pin "1") (pinfunction "1_1") (pintype "passive"))
    )
    (net (code "45") (name "GND") (class "Default")
      (node (ref "C11") (pin "2") (pinfunction "2_2") (pintype "passive"))
      (node (ref "C3") (pin "2") (pinfunction "2_2") (pintype "passive"))
      (node (ref "C32") (pin "2") (pinfunction "2_2") (pintype "passive"))
      (node (ref "C33") (pin "2") (pinfunction "2_2") (pintype "passive"))
      (node (ref "C4") (pin "2") (pinfunction "2_2") (pintype "passive"))
      (node (ref "C7") (pin "2") (pinfunction "2_2") (pintype "passive"))
      (node (ref "C8") (pin "1") (pinfunction "1_1") (pintype "passive"))
      (node (ref "H1") (pin "4") (pinfunction "GND_4") (pintype "passive"))
      (node (ref "J3") (pin "4") (pinfunction "GND_4") (pintype "input"))
      (node (ref "J7") (pin "2") (pinfunction "2_2") (pintype "passive"))
      (node (ref "JP2") (pin "10") (pinfunction "10_10") (pintype "passive"))
      (node (ref "JP2") (pin "3") (pinfunction "3_3") (pintype "passive"))
      (node (ref "JP2") (pin "4") (pinfunction "4_4") (pintype "passive"))
      (node (ref "JP2") (pin "6") (pinfunction "6_6") (pintype "passive"))
      (node (ref "JP2") (pin "8") (pinfunction "8_8") (pintype "passive"))
      (node (ref "L7") (pin "2") (pinfunction "2_2") (pintype "passive"))
      (node (ref "R15") (pin "1") (pinfunction "1_1") (pintype "passive"))
      (node (ref "R50") (pin "2") (pinfunction "2_2") (pintype "passive"))
      (node (ref "R51") (pin "2") (pinfunction "2_2") (pintype "passive"))
      (node (ref "R52") (pin "2") (pinfunction "2_2") (pintype "passive"))
      (node (ref "R53") (pin "2") (pinfunction "2_2") (pintype "passive"))
      (node (ref "U10") (pin "4") (pinfunction "GND_4") (pintype "power_in"))
      (node (ref "U2") (pin "2") (pinfunction "A_2") (pintype "passive"))
      (node (ref "U4") (pin "2") (pinfunction "K_2") (pintype "passive"))
      (node (ref "U5") (pin "2") (pinfunction "K_2") (pintype "passive"))
      (node (ref "U6") (pin "4") (pinfunction "E_4") (pintype "passive"))
      (node (ref "U8") (pin "21") (pinfunction "GND_21") (pintype "input"))
      (node (ref "U8") (pin "3") (pinfunction "AGND_3") (pintype "passive"))
      (node (ref "U8") (pin "5") (pinfunction "GND_5") (pintype "passive"))
      (node (ref "U9") (pin "10") (pinfunction "DGND_10") (pintype "passive"))
    )
    (net (code "46") (name "LAMP") (class "Default")
      (node (ref "C15") (pin "1") (pinfunction "1_1") (pintype "passive"))
      (node (ref "K1") (pin "2") (pinfunction "NC_2") (pintype "passive"))
      (node (ref "Q2") (pin "2") (pinfunction "T_2") (pintype "passive"))
      (node (ref "R17") (pin "2") (pinfunction "2_2") (pintype "passive"))
      (node (ref "R3") (pin "2") (pinfunction "2_2") (pintype "passive"))
    )
    (net (code "47") (name "NEUTRAL_IN") (class "Default")
      (node (ref "CT1") (pin "4") (pinfunction "ACout_4") (pintype "passive"))
      (node (ref "R32") (pin "2") (pinfunction "2_2") (pintype "passive"))
    )
    (net (code "48") (name "Net-(C9-Pad2)") (class "Default")
      (node (ref "C9") (pin "2") (pinfunction "2_2") (pintype "passive"))
      (node (ref "L3") (pin "2") (pinfunction "2_2") (pintype "passive"))
      (node (ref "L5") (pin "1") (pinfunction "1_1") (pintype "passive"))
      (node (ref "L6") (pin "2") (pinfunction "2_2") (pintype "passive"))
    )
    (net (code "49") (name "Net-(C15-Pad2)") (class "Default")
      (node (ref "C15") (pin "2") (pinfunction "2_2") (pintype "passive"))
      (node (ref "R18") (pin "2") (pinfunction "2_2") (pintype "passive"))
    )
    (net (code "50") (name "Net-(C20-Pad2)") (class "Default")
      (node (ref "C20") (pin "2") (pinfunction "2_2") (pintype "passive"))
      (node (ref "R28") (pin "2") (pinfunction "2_2") (pintype "passive"))
      (node (ref "R49") (pin "2") (pinfunction "2_2") (pintype "passive"))
    )
    (net (code "51") (name "Net-(C22-Pad1)") (class "Default")
      (node (ref "C22") (pin "1") (pinfunction "1_1") (pintype "passive"))
      (node (ref "R17") (pin "1") (pinfunction "1_1") (pintype "passive"))
      (node (ref "R20") (pin "1") (pinfunction "1_1") (pintype "passive"))
    )
    (net (code "52") (name "Net-(D1-K)") (class "Default")
      (node (ref "D1") (pin "2") (pinfunction "K_2") (pintype "passive"))
      (node (ref "R12") (pin "2") (pinfunction "2_2") (pintype "passive"))
    )
    (net (code "53") (name "Net-(D7-K)") (class "Default")
      (node (ref "D7") (pin "2") (pinfunction "K_2") (pintype "passive"))
      (node (ref "K1") (pin "4") (pinfunction "T1_4") (pintype "passive"))
      (node (ref "Q1") (pin "3") (pinfunction "C_3") (pintype "passive"))
      (node (ref "Q4") (pin "3") (pinfunction "C_3") (pintype "passive"))
    )
    (net (code "54") (name "Net-(D10-K)") (class "Default")
      (node (ref "D10") (pin "2") (pinfunction "K_2") (pintype "passive"))
      (node (ref "R5") (pin "1") (pinfunction "1_1") (pintype "passive"))
    )
    (net (code "55") (name "Net-(J2-+)") (class "Default")
      (node (ref "J2") (pin "1") (pinfunction "+_1") (pintype "passive"))
      (node (ref "R6") (pin "2") (pinfunction "2_2") (pintype "passive"))
    )
    (net (code "56") (name "Net-(J2--)") (class "Default")
      (node (ref "J2") (pin "4") (pinfunction "-_4") (pintype "passive"))
      (node (ref "R11") (pin "2") (pinfunction "2_2") (pintype "passive"))
    )
    (net (code "57") (name "Net-(J2-~-Pad2)") (class "Default")
      (node (ref "J2") (pin "2") (pinfunction "~_2") (pintype "passive"))
      (node (ref "R4") (pin "1") (pinfunction "1_1") (pintype "passive"))
    )
    (net (code "58") (name "Net-(J2-~-Pad3)") (class "Default")
      (node (ref "J2") (pin "3") (pinfunction "~_3") (pintype "passive"))
      (node (ref "R9") (pin "1") (pinfunction "1_1") (pintype "passive"))
    )
    (net (code "59") (name "Net-(LED1-Pad1)") (class "Default")
      (node (ref "LED1") (pin "1") (pinfunction "1_1") (pintype "passive"))
      (node (ref "R16") (pin "2") (pinfunction "2_2") (pintype "passive"))
    )
    (net (code "60") (name "Net-(LED2-Pad1)") (class "Default")
      (node (ref "LED2") (pin "1") (pinfunction "1_1") (pintype "passive"))
      (node (ref "R23") (pin "2") (pinfunction "2_2") (pintype "passive"))
    )
    (net (code "61") (name "Net-(LED3-Pad1)") (class "Default")
      (node (ref "LED3") (pin "1") (pinfunction "1_1") (pintype "passive"))
      (node (ref "R24") (pin "2") (pinfunction "2_2") (pintype "passive"))
    )
    (net (code "62") (name "Net-(LED4-Pad1)") (class "Default")
      (node (ref "LED4") (pin "1") (pinfunction "1_1") (pintype "passive"))
      (node (ref "R25") (pin "2") (pinfunction "2_2") (pintype "passive"))
    )
    (net (code "63") (name "Net-(Q1-B)") (class "Default")
      (node (ref "Q1") (pin "1") (pinfunction "B_1") (pintype "input"))
      (node (ref "R5") (pin "2") (pinfunction "2_2") (pintype "passive"))
      (node (ref "R7") (pin "1") (pinfunction "1_1") (pintype "passive"))
    )
    (net (code "64") (name "Net-(Q1-E)") (class "Default")
      (node (ref "Q1") (pin "2") (pinfunction "E_2") (pintype "passive"))
      (node (ref "Q4") (pin "1") (pinfunction "B_1") (pintype "input"))
    )
    (net (code "65") (name "Net-(Q2-G)") (class "Default")
      (node (ref "Q2") (pin "3") (pinfunction "G_3") (pintype "passive"))
      (node (ref "U4") (pin "4") (pinfunction "A/K_4") (pintype "passive"))
    )
    (net (code "66") (name "Net-(Q3-G)") (class "Default")
      (node (ref "Q3") (pin "3") (pinfunction "G_3") (pintype "passive"))
      (node (ref "U5") (pin "4") (pinfunction "A/K_4") (pintype "passive"))
    )
    (net (code "67") (name "Net-(R3-Pad1)") (class "Default")
      (node (ref "R3") (pin "1") (pinfunction "1_1") (pintype "passive"))
      (node (ref "R4") (pin "2") (pinfunction "2_2") (pintype "passive"))
    )
    (net (code "68") (name "Net-(R8-Pad1)") (class "Default")
      (node (ref "R8") (pin "1") (pinfunction "1_1") (pintype "passive"))
      (node (ref "R9") (pin "2") (pinfunction "2_2") (pintype "passive"))
    )
    (net (code "69") (name "Net-(R20-Pad2)") (class "Default")
      (node (ref "R20") (pin "2") (pinfunction "2_2") (pintype "passive"))
      (node (ref "U4") (pin "6") (pinfunction "A/K_6") (pintype "passive"))
    )
    (net (code "70") (name "Net-(R49-Pad1)") (class "Default")
      (node (ref "R49") (pin "1") (pinfunction "1_1") (pintype "passive"))
      (node (ref "U5") (pin "6") (pinfunction "A/K_6") (pintype "passive"))
    )
    (net (code "71") (name "Net-(U1-L)") (class "Default")
      (node (ref "C2") (pin "2") (pinfunction "2_2") (pintype "passive"))
      (node (ref "L4") (pin "2") (pinfunction "2_2") (pintype "passive"))
      (node (ref "R2") (pin "1") (pinfunction "1_1") (pintype "passive"))
      (node (ref "U1") (pin "3") (pinfunction "L_3") (pintype "passive"))
    )
    (net (code "72") (name "Net-(U2-R)") (class "Default")
      (node (ref "R14") (pin "1") (pinfunction "1_1") (pintype "passive"))
      (node (ref "R15") (pin "2") (pinfunction "2_2") (pintype "passive"))
      (node (ref "U2") (pin "3") (pinfunction "R_3") (pintype "passive"))
    )
    (net (code "73") (name "Net-(U4-A)") (class "Default")
      (node (ref "R22") (pin "1") (pinfunction "1_1") (pintype "passive"))
      (node (ref "U4") (pin "1") (pinfunction "A_1") (pintype "passive"))
    )
    (net (code "74") (name "Net-(U5-A)") (class "Default")
      (node (ref "R10") (pin "2") (pinfunction "2_2") (pintype "passive"))
      (node (ref "U5") (pin "1") (pinfunction "A_1") (pintype "passive"))
    )
    (net (code "75") (name "Net-(U6-A)") (class "Default")
      (node (ref "R6") (pin "1") (pinfunction "1_1") (pintype "passive"))
      (node (ref "U6") (pin "1") (pinfunction "A_1") (pintype "passive"))
    )
    (net (code "76") (name "Net-(U6-K)") (class "Default")
      (node (ref "R11") (pin "1") (pinfunction "1_1") (pintype "passive"))
      (node (ref "U6") (pin "2") (pinfunction "K_2") (pintype "passive"))
    )
    (net (code "77") (name "Net-(U8-PB6_(XTAL1{slash}TOSC1))") (class "Default")
      (node (ref "C3") (pin "1") (pinfunction "1_1") (pintype "passive"))
      (node (ref "U8") (pin "7") (pinfunction "PB6_(XTAL1/TOSC1)_7") (pintype "passive"))
      (node (ref "Y3") (pin "1") (pinfunction "1_1") (pintype "passive"))
    )
    (net (code "78") (name "Net-(U8-PB7_(XTAL2{slash}TOSC2))") (class "Default")
      (node (ref "C4") (pin "1") (pinfunction "1_1") (pintype "passive"))
      (node (ref "U8") (pin "8") (pinfunction "PB7_(XTAL2/TOSC2)_8") (pintype "passive"))
      (node (ref "Y3") (pin "2") (pinfunction "2_2") (pintype "passive"))
    )
    (net (code "79") (name "Net-(U9-CLK_IN)") (class "Default")
      (node (ref "C32") (pin "1") (pinfunction "1_1") (pintype "passive"))
      (node (ref "U9") (pin "15") (pinfunction "CLK_IN_15") (pintype "passive"))
      (node (ref "Y1") (pin "1") (pinfunction "1_1") (pintype "passive"))
    )
    (net (code "80") (name "Net-(U9-CLK_OUT)") (class "Default")
      (node (ref "C33") (pin "1") (pinfunction "1_1") (pintype "passive"))
      (node (ref "U9") (pin "16") (pinfunction "CLK_OUT_16") (pintype "passive"))
      (node (ref "Y1") (pin "2") (pinfunction "2_2") (pintype "passive"))
    )
    (net (code "81") (name "Net-(U9-DIN)") (class "Default")
      (node (ref "R42") (pin "2") (pinfunction "2_2") (pintype "passive"))
      (node (ref "R50") (pin "1") (pinfunction "1_1") (pintype "passive"))
      (node (ref "U9") (pin "20") (pinfunction "DIN_20") (pintype "passive"))
    )
    (net (code "82") (name "Net-(U9-DOUT)") (class "Default")
      (node (ref "R43") (pin "2") (pinfunction "2_2") (pintype "passive"))
      (node (ref "R51") (pin "1") (pinfunction "1_1") (pintype "passive"))
      (node (ref "U9") (pin "19") (pinfunction "DOUT_19") (pintype "passive"))
    )
    (net (code "83") (name "Net-(U9-REF_IN{slash}OUT)") (class "Default")
      (node (ref "C26") (pin "1") (pinfunction "1_1") (pintype "passive"))
      (node (ref "U9") (pin "9") (pinfunction "REF_IN/OUT_9") (pintype "passive"))
    )
    (net (code "84") (name "Net-(U9-SCLK)") (class "Default")
      (node (ref "R44") (pin "2") (pinfunction "2_2") (pintype "passive"))
      (node (ref "R52") (pin "1") (pinfunction "1_1") (pintype "passive"))
      (node (ref "U9") (pin "18") (pinfunction "SCLK_18") (pintype "passive"))
    )
    (net (code "85") (name "Net-(U9-V1N)") (class "Default")
      (node (ref "C28") (pin "1") (pinfunction "1_1") (pintype "passive"))
      (node (ref "R38") (pin "1") (pinfunction "1_1") (pintype "passive"))
      (node (ref "U9") (pin "5") (pinfunction "V1N_5") (pintype "passive"))
    )
    (net (code "86") (name "Net-(U9-V1P)") (class "Default")
      (node (ref "C27") (pin "1") (pinfunction "1_1") (pintype "passive"))
      (node (ref "R37") (pin "1") (pinfunction "1_1") (pintype "passive"))
      (node (ref "U9") (pin "4") (pinfunction "V1P_4") (pintype "passive"))
    )
    (net (code "87") (name "Net-(U9-V2N)") (class "Default")
      (node (ref "C29") (pin "1") (pinfunction "1_1") (pintype "passive"))
      (node (ref "R39") (pin "1") (pinfunction "1_1") (pintype "passive"))
      (node (ref "U9") (pin "6") (pinfunction "V2N_6") (pintype "passive"))
    )
    (net (code "88") (name "Net-(U9-V2P)") (class "Default")
      (node (ref "C30") (pin "1") (pinfunction "1_1") (pintype "passive"))
      (node (ref "R40") (pin "2") (pinfunction "2_2") (pintype "passive"))
      (node (ref "U9") (pin "7") (pinfunction "V2P_7") (pintype "passive"))
      (node (ref "VR2") (pin "2") (pinfunction "TAP_2") (pintype "passive"))
      (node (ref "VR2") (pin "3") (pinfunction "BOT_3") (pintype "passive"))
    )
    (net (code "89") (name "Net-(U9-~{CS})") (class "Default")
      (node (ref "R45") (pin "2") (pinfunction "2_2") (pintype "passive"))
      (node (ref "U9") (pin "17") (pinfunction "~{CS}_17") (pintype "passive"))
    )
    (net (code "90") (name "Net-(U9-~{RESET})") (class "Default")
      (node (ref "R1") (pin "1") (pinfunction "1_1") (pintype "passive"))
      (node (ref "U9") (pin "1") (pinfunction "~{RESET}_1") (pintype "passive"))
    )
    (net (code "91") (name "Net-(U10-X1)") (class "Default")
      (node (ref "U10") (pin "1") (pinfunction "X1_1") (pintype "input"))
      (node (ref "Y2") (pin "1") (pinfunction "OSC1_1") (pintype "passive"))
    )
    (net (code "92") (name "Net-(U10-X2)") (class "Default")
      (node (ref "U10") (pin "2") (pinfunction "X2_2") (pintype "output"))
      (node (ref "Y2") (pin "2") (pinfunction "OSC2_2") (pintype "passive"))
    )
    (net (code "93") (name "Net-(VR1-TAP)") (class "Default")
      (node (ref "R37") (pin "2") (pinfunction "2_2") (pintype "passive"))
      (node (ref "VR1") (pin "2") (pinfunction "TAP_2") (pintype "passive"))
    )
    (net (code "94") (name "Net-(VR2-TOP)") (class "Default")
      (node (ref "R36") (pin "1") (pinfunction "1_1") (pintype "passive"))
      (node (ref "VR2") (pin "1") (pinfunction "TOP_1") (pintype "passive"))
    )
    (net (code "95") (name "PHASE") (class "Default")
      (node (ref "C2") (pin "1") (pinfunction "1_1") (pintype "passive"))
      (node (ref "C9") (pin "1") (pinfunction "1_1") (pintype "passive"))
      (node (ref "F1") (pin "2") (pinfunction "2_2") (pintype "passive"))
      (node (ref "L4") (pin "1") (pinfunction "1_1") (pintype "passive"))
      (node (ref "R2") (pin "2") (pinfunction "2_2") (pintype "passive"))
      (node (ref "R32") (pin "1") (pinfunction "1_1") (pintype "passive"))
    )
    (net (code "96") (name "PHASEIN") (class "Default")
      (node (ref "F1") (pin "1") (pinfunction "1_1") (pintype "passive"))
    )
    (net (code "97") (name "PHASE_FIR") (class "Default")
      (node (ref "C20") (pin "1") (pinfunction "1_1") (pintype "passive"))
      (node (ref "C22") (pin "2") (pinfunction "2_2") (pintype "passive"))
      (node (ref "JP2000") (pin "2") (pinfunction "2_2") (pintype "passive"))
      (node (ref "K1") (pin "1") (pinfunction "COM_1") (pintype "passive"))
      (node (ref "Q2") (pin "1") (pinfunction "T_1") (pintype "passive"))
      (node (ref "Q3") (pin "1") (pinfunction "T_1") (pintype "passive"))
      (node (ref "R18") (pin "1") (pinfunction "1_1") (pintype "passive"))
      (node (ref "R36") (pin "2") (pinfunction "2_2") (pintype "passive"))
      (node (ref "R8") (pin "2") (pinfunction "2_2") (pintype "passive"))
    )
    (net (code "98") (name "POWERIN") (class "Default")
      (node (ref "D5") (pin "2") (pinfunction "2_2") (pintype "passive"))
      (node (ref "J1") (pin "1") (pinfunction "1_1") (pintype "passive"))
      (node (ref "Q4") (pin "2") (pinfunction "E_2") (pintype "passive"))
      (node (ref "R16") (pin "1") (pinfunction "1_1") (pintype "passive"))
      (node (ref "R7") (pin "2") (pinfunction "2_2") (pintype "passive"))
      (node (ref "U1") (pin "6") (pinfunction "+DC_OUT_6") (pintype "passive"))
      (node (ref "U3") (pin "1") (pinfunction "Vin_1") (pintype "passive"))
    )
    (net (code "99") (name "VDD5") (class "Default")
      (node (ref "C21") (pin "1") (pinfunction "1_1") (pintype "passive"))
      (node (ref "C23") (pin "2") (pinfunction "2_2") (pintype "passive"))
      (node (ref "C6") (pin "1") (pinfunction "1_1") (pintype "passive"))
      (node (ref "J1") (pin "29") (pinfunction "29_29") (pintype "passive"))
      (node (ref "L1") (pin "1") (pinfunction "1_1") (pintype "passive"))
      (node (ref "R26") (pin "1") (pinfunction "1_1") (pintype "passive"))
      (node (ref "R27") (pin "1") (pinfunction "1_1") (pintype "passive"))
      (node (ref "U3") (pin "3") (pinfunction "+5V_3") (pintype "passive"))
      (node (ref "U9") (pin "3") (pinfunction "AVDD_3") (pintype "passive"))
    )
    (net (code "100") (name "VDD5D") (class "Default")
      (node (ref "C11") (pin "1") (pinfunction "1_1") (pintype "passive"))
      (node (ref "C8") (pin "2") (pinfunction "2_2") (pintype "passive"))
      (node (ref "JP2") (pin "2") (pinfunction "2_2") (pintype "passive"))
      (node (ref "L1") (pin "2") (pinfunction "2_2") (pintype "passive"))
      (node (ref "R13") (pin "2") (pinfunction "2_2") (pintype "passive"))
      (node (ref "R21") (pin "2") (pinfunction "2_2") (pintype "passive"))
      (node (ref "R30") (pin "2") (pinfunction "2_2") (pintype "passive"))
      (node (ref "R46") (pin "2") (pinfunction "2_2") (pintype "passive"))
      (node (ref "R47") (pin "2") (pinfunction "2_2") (pintype "passive"))
      (node (ref "R48") (pin "2") (pinfunction "2_2") (pintype "passive"))
      (node (ref "U10") (pin "8") (pinfunction "VCC_8") (pintype "power_in"))
      (node (ref "U8") (pin "18") (pinfunction "AVCC_18") (pintype "passive"))
      (node (ref "U8") (pin "20") (pinfunction "AREF_20") (pintype "passive"))
      (node (ref "U8") (pin "4") (pinfunction "VCC_4") (pintype "passive"))
      (node (ref "U8") (pin "6") (pinfunction "VCC_6") (pintype "input"))
      (node (ref "U9") (pin "2") (pinfunction "DVDD_2") (pintype "passive"))
    )
    (net (code "101") (name "unconnected-(H1-Pad5)") (class "Default")
      (node (ref "H1") (pin "5") (pinfunction "5_5") (pintype "passive"))
    )
    (net (code "102") (name "unconnected-(H1-Pad6)") (class "Default")
      (node (ref "H1") (pin "6") (pinfunction "6_6") (pintype "passive"))
    )
    (net (code "103") (name "unconnected-(H1-VCC-Pad1)") (class "Default")
      (node (ref "H1") (pin "1") (pinfunction "VCC_1") (pintype "passive"))
    )
    (net (code "104") (name "unconnected-(J3-VCC-Pad1)") (class "Default")
      (node (ref "J3") (pin "1") (pinfunction "VCC_1") (pintype "input"))
    )
    (net (code "105") (name "unconnected-(K1-NO-Pad3)") (class "Default")
      (node (ref "K1") (pin "3") (pinfunction "NO_3") (pintype "passive"))
    )
    (net (code "106") (name "unconnected-(U8-ADC6-Pad19)") (class "Default")
      (node (ref "U8") (pin "19") (pinfunction "ADC6_19") (pintype "input"))
    )
    (net (code "107") (name "unconnected-(U8-ADC7-Pad22)") (class "Default")
      (node (ref "U8") (pin "22") (pinfunction "ADC7_22") (pintype "input"))
    )
    (net (code "108") (name "unconnected-(U8-PC0_(ADC0)-Pad23)") (class "Default")
      (node (ref "U8") (pin "23") (pinfunction "PC0_(ADC0)_23") (pintype "passive"))
    )
    (net (code "109") (name "unconnected-(U8-PC3_(ADC3)-Pad26)") (class "Default")
      (node (ref "U8") (pin "26") (pinfunction "PC3_(ADC3)_26") (pintype "passive"))
    )
    (net (code "110") (name "unconnected-(U8-PC4_(ADC4{slash}SDA)-Pad27)") (class "Default")
      (node (ref "U8") (pin "27") (pinfunction "PC4_(ADC4/SDA)_27") (pintype "passive"))
    )
    (net (code "111") (name "unconnected-(U8-PC5_(ADC5{slash}SCL)-Pad28)") (class "Default")
      (node (ref "U8") (pin "28") (pinfunction "PC5_(ADC5/SCL)_28") (pintype "passive"))
    )
    (net (code "112") (name "unconnected-(U8-PD4_(XCK{slash}T0)-Pad2)") (class "Default")
      (node (ref "U8") (pin "2") (pinfunction "PD4_(XCK/T0)_2") (pintype "passive"))
    )
    (net (code "113") (name "unconnected-(U8-PD7_(AIN1)-Pad11)") (class "Default")
      (node (ref "U8") (pin "11") (pinfunction "PD7_(AIN1)_11") (pintype "passive"))
    )
    (net (code "114") (name "unconnected-(U9-~{SAG}-Pad13)") (class "Default")
      (node (ref "U9") (pin "13") (pinfunction "~{SAG}_13") (pintype "passive"))
    )
  )
)
